# RedBoardCPU6809.net
KiCad netlist of a schematic drawn in EAGLE
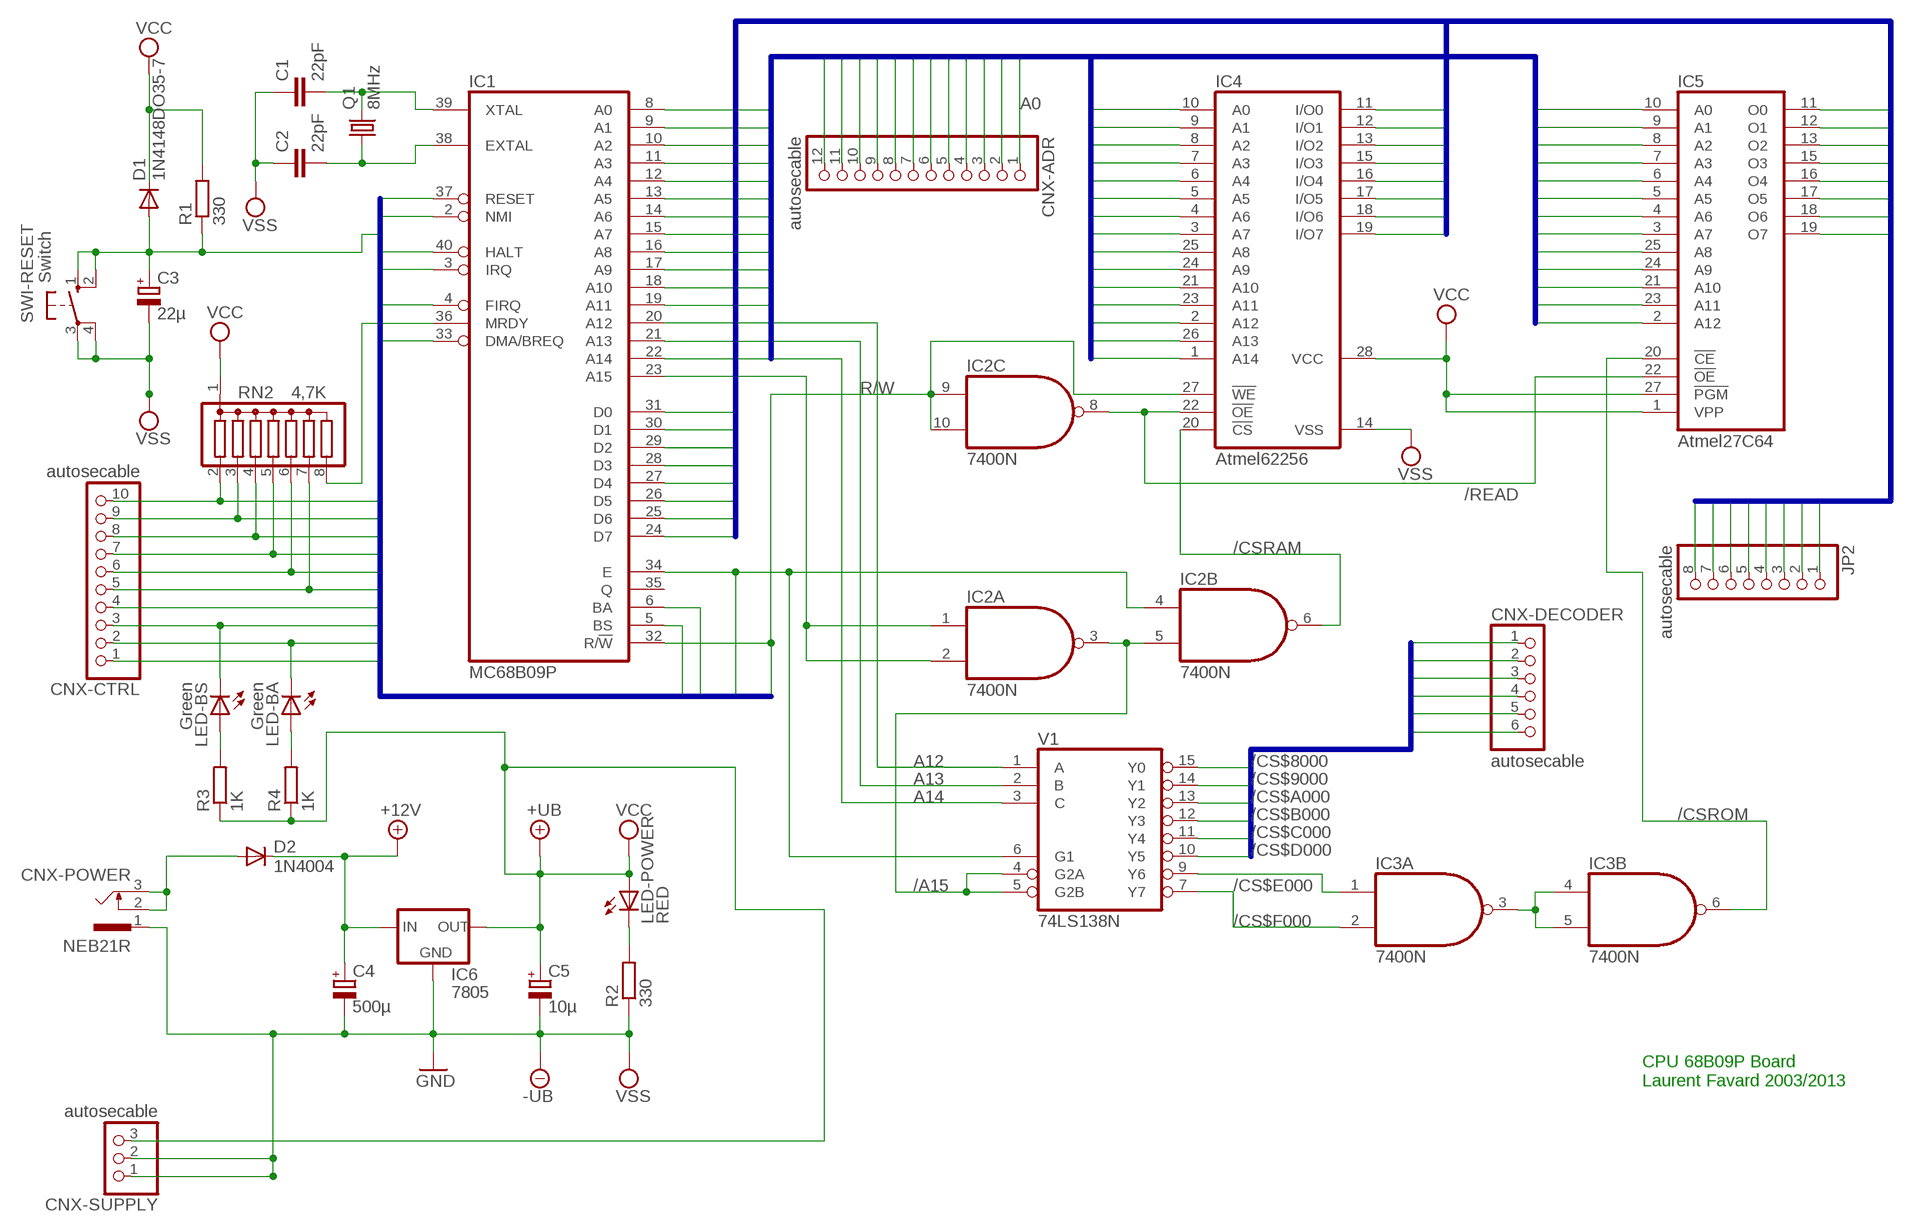
[diagram p0: schematic, sheet 1]

(export (version "E")
  (design (tool "Eeschema 10.0.6"))
  (components
    (comp (ref "C1")
      (value "22pF")
      (footprint "eagle-import:C2.5-3")
      (libsource (lib "eagle-import") (part "C2,5-3"))
    )
    (comp (ref "C2")
      (value "22pF")
      (footprint "eagle-import:C2.5-3")
      (libsource (lib "eagle-import") (part "C2,5-3"))
    )
    (comp (ref "C3")
      (value "22µ")
      (footprint "eagle-import:E2-5")
      (libsource (lib "eagle-import") (part "CPOL-EUE2-5"))
    )
    (comp (ref "C4")
      (value "500µ")
      (footprint "eagle-import:E2-5")
      (libsource (lib "eagle-import") (part "CPOL-EUE2-5"))
    )
    (comp (ref "C5")
      (value "10µ")
      (footprint "eagle-import:E2-5")
      (libsource (lib "eagle-import") (part "CPOL-EUE2-5"))
    )
    (comp (ref "CNX-ADR")
      (value "autosecable")
      (footprint "eagle-import:1X12")
      (libsource (lib "eagle-import") (part "PINHD-1X12"))
    )
    (comp (ref "CNX-CTRL")
      (value "autosecable")
      (footprint "eagle-import:1X10")
      (libsource (lib "eagle-import") (part "PINHD-1X10"))
    )
    (comp (ref "CNX-DECODER")
      (value "autosecable")
      (footprint "eagle-import:1X06")
      (libsource (lib "eagle-import") (part "PINHD-1X6"))
    )
    (comp (ref "CNX-POWER")
      (value "NEB21R")
      (footprint "eagle-import:NEB21R")
      (fields (field (name "MPN") "NEB 21 R"))
      (libsource (lib "eagle-import") (part "NEB21R"))
    )
    (comp (ref "CNX-SUPPLY")
      (value "autosecable")
      (footprint "eagle-import:1X03")
      (libsource (lib "eagle-import") (part "PINHD-1X3"))
    )
    (comp (ref "D1")
      (value "1N4148DO35-7")
      (footprint "eagle-import:DO35-7")
      (libsource (lib "eagle-import") (part "1N4148DO35-7"))
    )
    (comp (ref "D2")
      (value "1N4004")
      (footprint "eagle-import:DO41-10")
      (libsource (lib "eagle-import") (part "1N4004"))
    )
    (comp (ref "IC1")
      (value "MC68B09P")
      (footprint "eagle-import:DIL40")
      (fields (field (name "MF") "NTE ELECTRONICS") (field (name "MPN") "NTE6809"))
      (libsource (lib "eagle-import") (part "6809"))
    )
    (comp (ref "IC2")
      (value "7400N")
      (footprint "eagle-import:DIL14")
      (libsource (lib "eagle-import") (part "7400N"))
    )
    (comp (ref "IC3")
      (value "7400N")
      (footprint "eagle-import:DIL14")
      (libsource (lib "eagle-import") (part "7400N"))
    )
    (comp (ref "IC4")
      (value "Atmel62256")
      (footprint "eagle-import:DIL28-6")
      (libsource (lib "eagle-import") (part "62256P"))
    )
    (comp (ref "IC5")
      (value "Atmel27C64")
      (footprint "eagle-import:DIL28")
      (libsource (lib "eagle-import") (part "2764"))
    )
    (comp (ref "IC6")
      (value "7805")
      (footprint "eagle-import:78XXL")
      (libsource (lib "eagle-import") (part "78XXL"))
    )
    (comp (ref "JP2")
      (value "autosecable")
      (footprint "eagle-import:1X08")
      (libsource (lib "eagle-import") (part "PINHD-1X8"))
    )
    (comp (ref "LED-BA")
      (value "Green")
      (footprint "eagle-import:LED3MM")
      (libsource (lib "eagle-import") (part "LED3MM"))
    )
    (comp (ref "LED-BS")
      (value "Green")
      (footprint "eagle-import:LED3MM")
      (libsource (lib "eagle-import") (part "LED3MM"))
    )
    (comp (ref "LED-POWER")
      (value "RED")
      (footprint "eagle-import:LED3MM")
      (libsource (lib "eagle-import") (part "LED3MM"))
    )
    (comp (ref "Q1")
      (value "8MHz")
      (footprint "eagle-import:HC18U-H")
      (libsource (lib "eagle-import") (part "CRYSTALHC18U-H"))
    )
    (comp (ref "R1")
      (value "330")
      (footprint "eagle-import:0207_12")
      (libsource (lib "eagle-import") (part "R-EU_0207/12"))
    )
    (comp (ref "R2")
      (value "330")
      (footprint "eagle-import:0207_12")
      (libsource (lib "eagle-import") (part "R-EU_0207/12"))
    )
    (comp (ref "R3")
      (value "1K")
      (footprint "eagle-import:0207_12")
      (libsource (lib "eagle-import") (part "R-EU_0207/12"))
    )
    (comp (ref "R4")
      (value "1K")
      (footprint "eagle-import:0207_12")
      (libsource (lib "eagle-import") (part "R-EU_0207/12"))
    )
    (comp (ref "RN2")
      (value "4,7K")
      (footprint "eagle-import:SIL8")
      (libsource (lib "eagle-import") (part "G07R"))
    )
    (comp (ref "SWI-RESET")
      (value "Switch")
      (footprint "eagle-import:B3F-10XX")
      (fields (field (name "MPN") "B3F-1000"))
      (libsource (lib "eagle-import") (part "10-XX"))
    )
    (comp (ref "V1")
      (value "74LS138N")
      (footprint "eagle-import:DIL16")
      (libsource (lib "eagle-import") (part "74138NLS"))
    )
  )
  (nets
    (net (code "1") (name "+12V") (class "Default")
      (node (ref "C4") (pin "+") (pinfunction "+_+") (pintype "passive"))
      (node (ref "D2") (pin "C") (pinfunction "C_C") (pintype "passive"))
      (node (ref "IC6") (pin "IN") (pinfunction "IN_IN") (pintype "input"))
    )
    (net (code "2") (name "+UB") (class "Default")
      (node (ref "C5") (pin "+") (pinfunction "+_+") (pintype "passive"))
      (node (ref "CNX-SUPPLY") (pin "3") (pinfunction "3_3") (pintype "passive"))
      (node (ref "D1") (pin "C") (pinfunction "C_C") (pintype "passive"))
      (node (ref "IC4") (pin "28") (pinfunction "VCC_28") (pintype "power_in"))
      (node (ref "IC5") (pin "1") (pinfunction "VPP_1") (pintype "input"))
      (node (ref "IC5") (pin "27") (pinfunction "~{PGM}_27") (pintype "input"))
      (node (ref "IC6") (pin "OUT") (pinfunction "OUT_OUT") (pintype "passive"))
      (node (ref "LED-POWER") (pin "A") (pinfunction "A_A") (pintype "passive"))
      (node (ref "R1") (pin "2") (pinfunction "2_2") (pintype "passive"))
      (node (ref "R3") (pin "1") (pinfunction "1_1") (pintype "passive"))
      (node (ref "R4") (pin "1") (pinfunction "1_1") (pintype "passive"))
      (node (ref "RN2") (pin "1") (pinfunction "1_1") (pintype "passive"))
    )
    (net (code "3") (name "-UB") (class "Default")
      (node (ref "C1") (pin "1") (pinfunction "1_1") (pintype "passive"))
      (node (ref "C2") (pin "1") (pinfunction "1_1") (pintype "passive"))
      (node (ref "C3") (pin "-") (pinfunction "-_-") (pintype "passive"))
      (node (ref "C4") (pin "-") (pinfunction "-_-") (pintype "passive"))
      (node (ref "C5") (pin "-") (pinfunction "-_-") (pintype "passive"))
      (node (ref "CNX-POWER") (pin "1") (pinfunction "1_1") (pintype "passive"))
      (node (ref "CNX-SUPPLY") (pin "1") (pinfunction "1_1") (pintype "passive"))
      (node (ref "CNX-SUPPLY") (pin "2") (pinfunction "2_2") (pintype "passive"))
      (node (ref "IC4") (pin "14") (pinfunction "VSS_14") (pintype "power_in"))
      (node (ref "IC6") (pin "GND") (pinfunction "GND_GND") (pintype "input"))
      (node (ref "R2") (pin "1") (pinfunction "1_1") (pintype "passive"))
      (node (ref "SWI-RESET") (pin "3") (pinfunction "P_3") (pintype "passive"))
      (node (ref "SWI-RESET") (pin "4") (pinfunction "P1_4") (pintype "passive"))
    )
    (net (code "4") (name "/A0") (class "Default")
      (node (ref "CNX-ADR") (pin "1") (pinfunction "1_1") (pintype "passive"))
      (node (ref "IC1") (pin "8") (pinfunction "A0_8") (pintype "tri_state"))
      (node (ref "IC4") (pin "10") (pinfunction "A0_10") (pintype "input"))
      (node (ref "IC5") (pin "10") (pinfunction "A0_10") (pintype "input"))
    )
    (net (code "5") (name "/A1") (class "Default")
      (node (ref "CNX-ADR") (pin "2") (pinfunction "2_2") (pintype "passive"))
      (node (ref "IC1") (pin "9") (pinfunction "A1_9") (pintype "tri_state"))
      (node (ref "IC4") (pin "9") (pinfunction "A1_9") (pintype "input"))
      (node (ref "IC5") (pin "9") (pinfunction "A1_9") (pintype "input"))
    )
    (net (code "6") (name "/A2") (class "Default")
      (node (ref "CNX-ADR") (pin "3") (pinfunction "3_3") (pintype "passive"))
      (node (ref "IC1") (pin "10") (pinfunction "A2_10") (pintype "tri_state"))
      (node (ref "IC4") (pin "8") (pinfunction "A2_8") (pintype "input"))
      (node (ref "IC5") (pin "8") (pinfunction "A2_8") (pintype "input"))
    )
    (net (code "7") (name "/A3") (class "Default")
      (node (ref "CNX-ADR") (pin "4") (pinfunction "4_4") (pintype "passive"))
      (node (ref "IC1") (pin "11") (pinfunction "A3_11") (pintype "tri_state"))
      (node (ref "IC4") (pin "7") (pinfunction "A3_7") (pintype "input"))
      (node (ref "IC5") (pin "7") (pinfunction "A3_7") (pintype "input"))
    )
    (net (code "8") (name "/A4") (class "Default")
      (node (ref "CNX-ADR") (pin "5") (pinfunction "5_5") (pintype "passive"))
      (node (ref "IC1") (pin "12") (pinfunction "A4_12") (pintype "tri_state"))
      (node (ref "IC4") (pin "6") (pinfunction "A4_6") (pintype "input"))
      (node (ref "IC5") (pin "6") (pinfunction "A4_6") (pintype "input"))
    )
    (net (code "9") (name "/A5") (class "Default")
      (node (ref "CNX-ADR") (pin "6") (pinfunction "6_6") (pintype "passive"))
      (node (ref "IC1") (pin "13") (pinfunction "A5_13") (pintype "tri_state"))
      (node (ref "IC4") (pin "5") (pinfunction "A5_5") (pintype "input"))
      (node (ref "IC5") (pin "5") (pinfunction "A5_5") (pintype "input"))
    )
    (net (code "10") (name "/A6") (class "Default")
      (node (ref "CNX-ADR") (pin "7") (pinfunction "7_7") (pintype "passive"))
      (node (ref "IC1") (pin "14") (pinfunction "A6_14") (pintype "tri_state"))
      (node (ref "IC4") (pin "4") (pinfunction "A6_4") (pintype "input"))
      (node (ref "IC5") (pin "4") (pinfunction "A6_4") (pintype "input"))
    )
    (net (code "11") (name "/A7") (class "Default")
      (node (ref "CNX-ADR") (pin "8") (pinfunction "8_8") (pintype "passive"))
      (node (ref "IC1") (pin "15") (pinfunction "A7_15") (pintype "tri_state"))
      (node (ref "IC4") (pin "3") (pinfunction "A7_3") (pintype "input"))
      (node (ref "IC5") (pin "3") (pinfunction "A7_3") (pintype "input"))
    )
    (net (code "12") (name "/A8") (class "Default")
      (node (ref "CNX-ADR") (pin "9") (pinfunction "9_9") (pintype "passive"))
      (node (ref "IC1") (pin "16") (pinfunction "A8_16") (pintype "tri_state"))
      (node (ref "IC4") (pin "25") (pinfunction "A8_25") (pintype "input"))
      (node (ref "IC5") (pin "25") (pinfunction "A8_25") (pintype "input"))
    )
    (net (code "13") (name "/A9") (class "Default")
      (node (ref "CNX-ADR") (pin "10") (pinfunction "10_10") (pintype "passive"))
      (node (ref "IC1") (pin "17") (pinfunction "A9_17") (pintype "tri_state"))
      (node (ref "IC4") (pin "24") (pinfunction "A9_24") (pintype "input"))
      (node (ref "IC5") (pin "24") (pinfunction "A9_24") (pintype "input"))
    )
    (net (code "14") (name "/A10") (class "Default")
      (node (ref "CNX-ADR") (pin "11") (pinfunction "11_11") (pintype "passive"))
      (node (ref "IC1") (pin "18") (pinfunction "A10_18") (pintype "tri_state"))
      (node (ref "IC4") (pin "21") (pinfunction "A10_21") (pintype "input"))
      (node (ref "IC5") (pin "21") (pinfunction "A10_21") (pintype "input"))
    )
    (net (code "15") (name "/A11") (class "Default")
      (node (ref "CNX-ADR") (pin "12") (pinfunction "12_12") (pintype "passive"))
      (node (ref "IC1") (pin "19") (pinfunction "A11_19") (pintype "tri_state"))
      (node (ref "IC4") (pin "23") (pinfunction "A11_23") (pintype "input"))
      (node (ref "IC5") (pin "23") (pinfunction "A11_23") (pintype "input"))
    )
    (net (code "16") (name "/A12") (class "Default")
      (node (ref "IC1") (pin "20") (pinfunction "A12_20") (pintype "tri_state"))
      (node (ref "IC4") (pin "2") (pinfunction "A12_2") (pintype "input"))
      (node (ref "IC5") (pin "2") (pinfunction "A12_2") (pintype "input"))
      (node (ref "V1") (pin "1") (pinfunction "A_1") (pintype "input"))
    )
    (net (code "17") (name "/A13") (class "Default")
      (node (ref "IC1") (pin "21") (pinfunction "A13_21") (pintype "tri_state"))
      (node (ref "IC4") (pin "26") (pinfunction "A13_26") (pintype "input"))
      (node (ref "V1") (pin "2") (pinfunction "B_2") (pintype "input"))
    )
    (net (code "18") (name "/A14") (class "Default")
      (node (ref "IC1") (pin "22") (pinfunction "A14_22") (pintype "tri_state"))
      (node (ref "IC4") (pin "1") (pinfunction "A14_1") (pintype "input"))
      (node (ref "V1") (pin "3") (pinfunction "C_3") (pintype "input"))
    )
    (net (code "19") (name "/BA") (class "Default")
      (node (ref "CNX-CTRL") (pin "2") (pinfunction "2_2") (pintype "passive"))
      (node (ref "IC1") (pin "6") (pinfunction "BA_6") (pintype "output"))
      (node (ref "LED-BA") (pin "K") (pinfunction "C_K") (pintype "passive"))
    )
    (net (code "20") (name "/BS") (class "Default")
      (node (ref "CNX-CTRL") (pin "3") (pinfunction "3_3") (pintype "passive"))
      (node (ref "IC1") (pin "5") (pinfunction "BS_5") (pintype "output"))
      (node (ref "LED-BS") (pin "K") (pinfunction "C_K") (pintype "passive"))
    )
    (net (code "21") (name "/D0") (class "Default")
      (node (ref "IC1") (pin "31") (pinfunction "D0_31") (pintype "bidirectional"))
      (node (ref "IC4") (pin "11") (pinfunction "I/O0_11") (pintype "bidirectional"))
      (node (ref "IC5") (pin "11") (pinfunction "O0_11") (pintype "tri_state"))
      (node (ref "JP2") (pin "1") (pinfunction "1_1") (pintype "passive"))
    )
    (net (code "22") (name "/D1") (class "Default")
      (node (ref "IC1") (pin "30") (pinfunction "D1_30") (pintype "bidirectional"))
      (node (ref "IC4") (pin "12") (pinfunction "I/O1_12") (pintype "bidirectional"))
      (node (ref "IC5") (pin "12") (pinfunction "O1_12") (pintype "tri_state"))
      (node (ref "JP2") (pin "2") (pinfunction "2_2") (pintype "passive"))
    )
    (net (code "23") (name "/D2") (class "Default")
      (node (ref "IC1") (pin "29") (pinfunction "D2_29") (pintype "bidirectional"))
      (node (ref "IC4") (pin "13") (pinfunction "I/O2_13") (pintype "bidirectional"))
      (node (ref "IC5") (pin "13") (pinfunction "O2_13") (pintype "tri_state"))
      (node (ref "JP2") (pin "3") (pinfunction "3_3") (pintype "passive"))
    )
    (net (code "24") (name "/D3") (class "Default")
      (node (ref "IC1") (pin "28") (pinfunction "D3_28") (pintype "bidirectional"))
      (node (ref "IC4") (pin "15") (pinfunction "I/O3_15") (pintype "bidirectional"))
      (node (ref "JP2") (pin "4") (pinfunction "4_4") (pintype "passive"))
    )
    (net (code "25") (name "/D4") (class "Default")
      (node (ref "IC1") (pin "27") (pinfunction "D4_27") (pintype "bidirectional"))
      (node (ref "IC4") (pin "16") (pinfunction "I/O4_16") (pintype "bidirectional"))
      (node (ref "IC5") (pin "15") (pinfunction "O3_15") (pintype "tri_state"))
      (node (ref "IC5") (pin "16") (pinfunction "O4_16") (pintype "tri_state"))
      (node (ref "JP2") (pin "5") (pinfunction "5_5") (pintype "passive"))
    )
    (net (code "26") (name "/D5") (class "Default")
      (node (ref "IC1") (pin "26") (pinfunction "D5_26") (pintype "bidirectional"))
      (node (ref "IC5") (pin "17") (pinfunction "O5_17") (pintype "tri_state"))
      (node (ref "JP2") (pin "6") (pinfunction "6_6") (pintype "passive"))
    )
    (net (code "27") (name "/D6") (class "Default")
      (node (ref "IC1") (pin "25") (pinfunction "D6_25") (pintype "bidirectional"))
      (node (ref "IC4") (pin "18") (pinfunction "I/O6_18") (pintype "bidirectional"))
      (node (ref "IC5") (pin "18") (pinfunction "O6_18") (pintype "tri_state"))
      (node (ref "JP2") (pin "7") (pinfunction "7_7") (pintype "passive"))
    )
    (net (code "28") (name "/D7") (class "Default")
      (node (ref "IC1") (pin "24") (pinfunction "D7_24") (pintype "bidirectional"))
      (node (ref "IC4") (pin "17") (pinfunction "I/O5_17") (pintype "bidirectional"))
      (node (ref "IC4") (pin "19") (pinfunction "I/O7_19") (pintype "bidirectional"))
      (node (ref "IC5") (pin "19") (pinfunction "O7_19") (pintype "tri_state"))
      (node (ref "JP2") (pin "8") (pinfunction "8_8") (pintype "passive"))
    )
    (net (code "29") (name "/DMA{slash}BREQ") (class "Default")
      (node (ref "CNX-CTRL") (pin "5") (pinfunction "5_5") (pintype "passive"))
      (node (ref "IC1") (pin "33") (pinfunction "DMA/BREQ_33") (pintype "input"))
      (node (ref "RN2") (pin "7") (pinfunction "7_7") (pintype "passive"))
    )
    (net (code "30") (name "/E") (class "Default")
      (node (ref "CNX-CTRL") (pin "1") (pinfunction "1_1") (pintype "passive"))
      (node (ref "IC1") (pin "34") (pinfunction "E_34") (pintype "output"))
      (node (ref "IC2") (pin "4") (pinfunction "I0_4") (pintype "input"))
      (node (ref "V1") (pin "6") (pinfunction "G1_6") (pintype "input"))
    )
    (net (code "31") (name "/FIRQ") (class "Default")
      (node (ref "CNX-CTRL") (pin "6") (pinfunction "6_6") (pintype "passive"))
      (node (ref "IC1") (pin "4") (pinfunction "FIRQ_4") (pintype "input"))
      (node (ref "RN2") (pin "6") (pinfunction "6_6") (pintype "passive"))
    )
    (net (code "32") (name "/HALT") (class "Default")
      (node (ref "CNX-CTRL") (pin "8") (pinfunction "8_8") (pintype "passive"))
      (node (ref "IC1") (pin "40") (pinfunction "HALT_40") (pintype "input"))
      (node (ref "RN2") (pin "4") (pinfunction "4_4") (pintype "passive"))
    )
    (net (code "33") (name "/IRQ") (class "Default")
      (node (ref "CNX-CTRL") (pin "7") (pinfunction "7_7") (pintype "passive"))
      (node (ref "IC1") (pin "3") (pinfunction "IRQ_3") (pintype "input"))
      (node (ref "RN2") (pin "5") (pinfunction "5_5") (pintype "passive"))
    )
    (net (code "34") (name "/NMI") (class "Default")
      (node (ref "CNX-CTRL") (pin "9") (pinfunction "9_9") (pintype "passive"))
      (node (ref "IC1") (pin "2") (pinfunction "NMI_2") (pintype "input"))
      (node (ref "RN2") (pin "3") (pinfunction "3_3") (pintype "passive"))
    )
    (net (code "35") (name "/RESET") (class "Default")
      (node (ref "C3") (pin "+") (pinfunction "+_+") (pintype "passive"))
      (node (ref "CNX-CTRL") (pin "10") (pinfunction "10_10") (pintype "passive"))
      (node (ref "D1") (pin "A") (pinfunction "A_A") (pintype "passive"))
      (node (ref "IC1") (pin "37") (pinfunction "RESET_37") (pintype "input"))
      (node (ref "R1") (pin "1") (pinfunction "1_1") (pintype "passive"))
      (node (ref "RN2") (pin "2") (pinfunction "2_2") (pintype "passive"))
      (node (ref "SWI-RESET") (pin "1") (pinfunction "S_1") (pintype "passive"))
      (node (ref "SWI-RESET") (pin "2") (pinfunction "S1_2") (pintype "passive"))
    )
    (net (code "36") (name "/R{slash}W") (class "Default")
      (node (ref "CNX-CTRL") (pin "4") (pinfunction "4_4") (pintype "passive"))
      (node (ref "IC1") (pin "32") (pinfunction "R/~{W}_32") (pintype "output"))
      (node (ref "IC2") (pin "10") (pinfunction "I1_10") (pintype "input"))
      (node (ref "IC2") (pin "9") (pinfunction "I0_9") (pintype "input"))
      (node (ref "IC4") (pin "27") (pinfunction "~{WE}_27") (pintype "input"))
    )
    (net (code "37") (name "/{slash}A15") (class "Default")
      (node (ref "IC2") (pin "3") (pinfunction "O_3") (pintype "output"))
      (node (ref "IC2") (pin "5") (pinfunction "I1_5") (pintype "input"))
      (node (ref "V1") (pin "4") (pinfunction "G2A_4") (pintype "input"))
      (node (ref "V1") (pin "5") (pinfunction "G2B_5") (pintype "input"))
    )
    (net (code "38") (name "/{slash}CS$8000") (class "Default")
      (node (ref "CNX-DECODER") (pin "1") (pinfunction "1_1") (pintype "passive"))
      (node (ref "V1") (pin "15") (pinfunction "Y0_15") (pintype "output"))
    )
    (net (code "39") (name "/{slash}CS$9000") (class "Default")
      (node (ref "CNX-DECODER") (pin "2") (pinfunction "2_2") (pintype "passive"))
      (node (ref "V1") (pin "14") (pinfunction "Y1_14") (pintype "output"))
    )
    (net (code "40") (name "/{slash}CS$A000") (class "Default")
      (node (ref "CNX-DECODER") (pin "3") (pinfunction "3_3") (pintype "passive"))
      (node (ref "V1") (pin "13") (pinfunction "Y2_13") (pintype "output"))
    )
    (net (code "41") (name "/{slash}CS$B000") (class "Default")
      (node (ref "CNX-DECODER") (pin "4") (pinfunction "4_4") (pintype "passive"))
      (node (ref "V1") (pin "12") (pinfunction "Y3_12") (pintype "output"))
    )
    (net (code "42") (name "/{slash}CS$C000") (class "Default")
      (node (ref "CNX-DECODER") (pin "5") (pinfunction "5_5") (pintype "passive"))
      (node (ref "V1") (pin "11") (pinfunction "Y4_11") (pintype "output"))
    )
    (net (code "43") (name "/{slash}CS$D000") (class "Default")
      (node (ref "CNX-DECODER") (pin "6") (pinfunction "6_6") (pintype "passive"))
      (node (ref "V1") (pin "10") (pinfunction "Y5_10") (pintype "output"))
    )
    (net (code "44") (name "/{slash}CS$E000") (class "Default")
      (node (ref "IC3") (pin "1") (pinfunction "I0_1") (pintype "input"))
      (node (ref "V1") (pin "9") (pinfunction "Y6_9") (pintype "output"))
    )
    (net (code "45") (name "/{slash}CS$F000") (class "Default")
      (node (ref "IC3") (pin "2") (pinfunction "I1_2") (pintype "input"))
      (node (ref "V1") (pin "7") (pinfunction "Y7_7") (pintype "output"))
    )
    (net (code "46") (name "/{slash}CSRAM") (class "Default")
      (node (ref "IC2") (pin "6") (pinfunction "O_6") (pintype "output"))
      (node (ref "IC4") (pin "20") (pinfunction "~{CS}_20") (pintype "input"))
    )
    (net (code "47") (name "/{slash}CSROM") (class "Default")
      (node (ref "IC3") (pin "6") (pinfunction "O_6") (pintype "output"))
      (node (ref "IC5") (pin "20") (pinfunction "~{CE}_20") (pintype "input"))
    )
    (net (code "48") (name "/{slash}READ") (class "Default")
      (node (ref "IC2") (pin "8") (pinfunction "O_8") (pintype "output"))
      (node (ref "IC4") (pin "22") (pinfunction "~{OE}_22") (pintype "input"))
      (node (ref "IC5") (pin "22") (pinfunction "~{OE}_22") (pintype "input"))
    )
    (net (code "49") (name "Net-(CNX-POWER-Pad2)") (class "Default")
      (node (ref "CNX-POWER") (pin "2") (pinfunction "2_2") (pintype "passive"))
      (node (ref "CNX-POWER") (pin "3") (pinfunction "3_3") (pintype "passive"))
      (node (ref "D2") (pin "A") (pinfunction "A_A") (pintype "passive"))
    )
    (net (code "50") (name "Net-(IC1A-A15)") (class "Default")
      (node (ref "IC1") (pin "23") (pinfunction "A15_23") (pintype "tri_state"))
      (node (ref "IC2") (pin "1") (pinfunction "I0_1") (pintype "input"))
      (node (ref "IC2") (pin "2") (pinfunction "I1_2") (pintype "input"))
    )
    (net (code "51") (name "Net-(IC1A-EXTAL)") (class "Default")
      (node (ref "C2") (pin "2") (pinfunction "2_2") (pintype "passive"))
      (node (ref "IC1") (pin "38") (pinfunction "EXTAL_38") (pintype "input"))
      (node (ref "Q1") (pin "1") (pinfunction "1_1") (pintype "passive"))
    )
    (net (code "52") (name "Net-(IC1A-MRDY)") (class "Default")
      (node (ref "IC1") (pin "36") (pinfunction "MRDY_36") (pintype "input"))
      (node (ref "RN2") (pin "8") (pinfunction "8_8") (pintype "passive"))
    )
    (net (code "53") (name "Net-(IC1A-XTAL)") (class "Default")
      (node (ref "C1") (pin "2") (pinfunction "2_2") (pintype "passive"))
      (node (ref "IC1") (pin "39") (pinfunction "XTAL_39") (pintype "input"))
      (node (ref "Q1") (pin "2") (pinfunction "2_2") (pintype "passive"))
    )
    (net (code "54") (name "Net-(IC3A-O)") (class "Default")
      (node (ref "IC3") (pin "3") (pinfunction "O_3") (pintype "output"))
      (node (ref "IC3") (pin "4") (pinfunction "I0_4") (pintype "input"))
      (node (ref "IC3") (pin "5") (pinfunction "I1_5") (pintype "input"))
    )
    (net (code "55") (name "Net-(LED-BA-PadA)") (class "Default")
      (node (ref "LED-BA") (pin "A") (pinfunction "A_A") (pintype "passive"))
      (node (ref "R4") (pin "2") (pinfunction "2_2") (pintype "passive"))
    )
    (net (code "56") (name "Net-(LED-BS-PadA)") (class "Default")
      (node (ref "LED-BS") (pin "A") (pinfunction "A_A") (pintype "passive"))
      (node (ref "R3") (pin "2") (pinfunction "2_2") (pintype "passive"))
    )
    (net (code "57") (name "Net-(LED-POWER-C)") (class "Default")
      (node (ref "LED-POWER") (pin "K") (pinfunction "C_K") (pintype "passive"))
      (node (ref "R2") (pin "2") (pinfunction "2_2") (pintype "passive"))
    )
    (net (code "58") (name "unconnected-(IC1A-Q-Pad35)") (class "Default")
      (node (ref "IC1") (pin "35") (pinfunction "Q_35") (pintype "output"))
    )
  )
)
